# NVME.net
KiCad netlist of a schematic drawn in Altium Designer
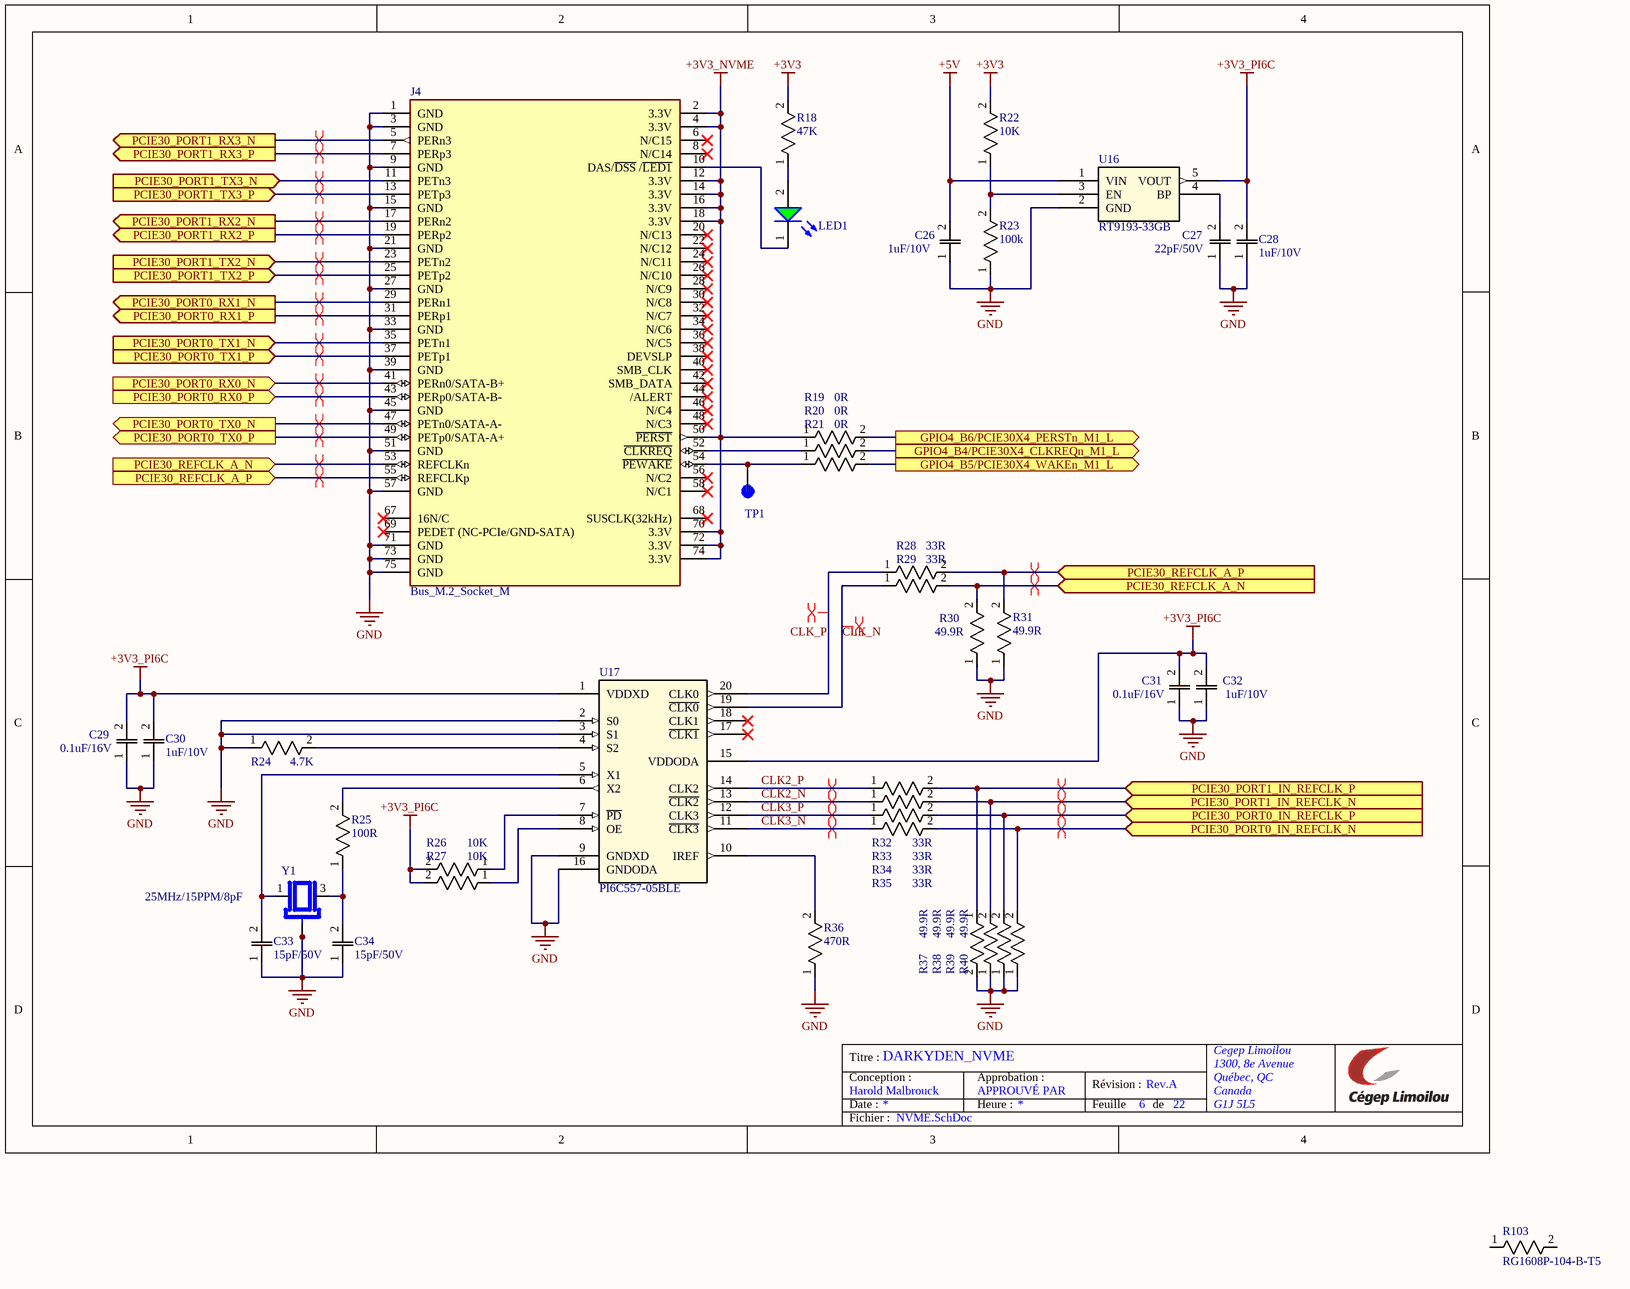
[diagram p0: NVME.SchDoc]

(export (version "E")
  (design (tool "Eeschema 10.0.6"))
  (components
    (comp (ref "C26")
      (value "1uF/10V")
      (footprint "CAPC220145_100N_KEM")
      (description "Multilayer Ceramic Capacitors MLCC - SMD/SMT 10V 1uF X7R 0805 10%")
      (fields
        (field (name "MANUFACTURER") "KEMET")
        (field (name "MANUFACTURER PART NUMBER") "C0805C105K8RACTU")
      )
      (libsource (lib "C0805C105K8RACTU") (part "C0805C105K8RACTU"))
    )
    (comp (ref "C27")
      (value "22pF/50V")
      (footprint "CAPC220145_145N_KEM")
      (description "Cap Ceramic 22pF 50V X7R 5% Pad SMD 0805 125°C T/R")
      (fields
        (field (name "MANUFACTURER") "KEMET")
        (field (name "MANUFACTURER PART NUMBER") "C0805C220J5RACTU")
      )
      (libsource (lib "C0805C220J5RACTU") (part "C0805C220J5RACTU"))
    )
    (comp (ref "C28")
      (value "1uF/10V")
      (footprint "CAPC220145_100N_KEM")
      (description "Multilayer Ceramic Capacitors MLCC - SMD/SMT 10V 1uF X7R 0805 10%")
      (fields
        (field (name "MANUFACTURER") "KEMET")
        (field (name "MANUFACTURER PART NUMBER") "C0805C105K8RACTU")
      )
      (libsource (lib "C0805C105K8RACTU") (part "C0805C105K8RACTU"))
    )
    (comp (ref "C29")
      (value "0.1uF/16V")
      (footprint "CAPC220145_88N_KEM")
      (description "0805 (2012METRIC) Ceramic Capacitor SMD Auto X7R 16V 0.1MUF ±10% X7R")
      (fields
        (field (name "MANUFACTURER") "KEMET")
        (field (name "MANUFACTURER PART NUMBER") "C0805C104K4RACAUTO")
      )
      (libsource (lib "C0805C104K4RACAUTO") (part "C0805C104K4RACAUTO"))
    )
    (comp (ref "C30")
      (value "1uF/10V")
      (footprint "CAPC220145_100N_KEM")
      (description "Multilayer Ceramic Capacitors MLCC - SMD/SMT 10V 1uF X7R 0805 10%")
      (fields
        (field (name "MANUFACTURER") "KEMET")
        (field (name "MANUFACTURER PART NUMBER") "C0805C105K8RACTU")
      )
      (libsource (lib "C0805C105K8RACTU") (part "C0805C105K8RACTU"))
    )
    (comp (ref "C31")
      (value "0.1uF/16V")
      (footprint "CAPC220145_88N_KEM")
      (description "0805 (2012METRIC) Ceramic Capacitor SMD Auto X7R 16V 0.1MUF ±10% X7R")
      (fields
        (field (name "MANUFACTURER") "KEMET")
        (field (name "MANUFACTURER PART NUMBER") "C0805C104K4RACAUTO")
      )
      (libsource (lib "C0805C104K4RACAUTO") (part "C0805C104K4RACAUTO"))
    )
    (comp (ref "C32")
      (value "1uF/10V")
      (footprint "CAPC220145_100N_KEM")
      (description "Multilayer Ceramic Capacitors MLCC - SMD/SMT 10V 1uF X7R 0805 10%")
      (fields
        (field (name "MANUFACTURER") "KEMET")
        (field (name "MANUFACTURER PART NUMBER") "C0805C105K8RACTU")
      )
      (libsource (lib "C0805C105K8RACTU") (part "C0805C105K8RACTU"))
    )
    (comp (ref "C33")
      (value "15pF/50V")
      (footprint "CAPC220145_88N_KEM")
      (description "Multilayer Ceramic Capacitors MLCC - SMD/SMT 50V 15pF X7R 0805 10% AEC-Q200")
      (fields
        (field (name "MANUFACTURER") "KEMET")
        (field (name "MANUFACTURER PART NUMBER") "C0805C150K5RACAUTO")
      )
      (libsource (lib "C0805C150K5RACAUTO") (part "C0805C150K5RACAUTO"))
    )
    (comp (ref "C34")
      (value "15pF/50V")
      (footprint "CAPC220145_88N_KEM")
      (description "Multilayer Ceramic Capacitors MLCC - SMD/SMT 50V 15pF X7R 0805 10% AEC-Q200")
      (fields
        (field (name "MANUFACTURER") "KEMET")
        (field (name "MANUFACTURER PART NUMBER") "C0805C150K5RACAUTO")
      )
      (libsource (lib "C0805C150K5RACAUTO") (part "C0805C150K5RACAUTO"))
    )
    (comp (ref "J4")
      (value "Bus_M.2_Socket_M")
      (footprint "AMPHENOL_MDT420M03001")
      (fields (field (name "MF") "Amphenol Commercial") (field (name "MP") "MDT420M03001"))
      (libsource (lib "Bus_M.2_Socket_M") (part "Bus_M.2_Socket_M"))
    )
    (comp (ref "LED1")
      (value "Green, 3.2V, 140°")
      (footprint "WL-SMCD_0603")
      (description "WL-SMCD Mono-color Chip LED Diffused, SMT, size 0603, Green, 3.2V, 140°")
      (fields
        (field (name "MANUFACTURER PART NUMBER") "150060GS55040")
        (field (name "MANUFACTURER") "Wurth Elektronik")
      )
      (libsource (lib "0603_LED") (part "GREEN"))
    )
    (comp (ref "R18")
      (value "47K")
      (footprint "RC0603N_PAN")
      (description "Resistor Thick Film 0603 47K Ohm 5% 1/10W 200ppm/C Molded SMD Punched Carrier T/R")
      (fields
        (field (name "MANUFACTURER") "Panasonic")
        (field (name "MANUFACTURER PART NUMBER") "ERJ-3GEYJ473V")
      )
      (libsource (lib "ERJ-3GEYJ473V") (part "ERJ-3GEYJ473V"))
    )
    (comp (ref "R19")
      (value "0R")
      (footprint "SamacSys:ERJ3EKF1000V")
      (description "Zero Ohm Resistor, Jumper, 0603 [1608 Metric], Thick Film, 100 mW, 1 A, Surface Mount")
      (fields
        (field (name "MANUFACTURER_PART_NUMBER") "ERJ-3GEY0R00V")
        (field (name "MOUSER PART NUMBER") "667-ERJ-3GEY0R00V")
      )
      (libsource (lib "SamacSys") (part "ERJ-3GEY0R00V"))
    )
    (comp (ref "R20")
      (value "0R")
      (footprint "SamacSys:ERJ3EKF1000V")
      (description "Zero Ohm Resistor, Jumper, 0603 [1608 Metric], Thick Film, 100 mW, 1 A, Surface Mount")
      (fields
        (field (name "MANUFACTURER_PART_NUMBER") "ERJ-3GEY0R00V")
        (field (name "MOUSER PART NUMBER") "667-ERJ-3GEY0R00V")
      )
      (libsource (lib "SamacSys") (part "ERJ-3GEY0R00V"))
    )
    (comp (ref "R21")
      (value "0R")
      (footprint "SamacSys:ERJ3EKF1000V")
      (description "Zero Ohm Resistor, Jumper, 0603 [1608 Metric], Thick Film, 100 mW, 1 A, Surface Mount")
      (fields
        (field (name "MANUFACTURER_PART_NUMBER") "ERJ-3GEY0R00V")
        (field (name "MOUSER PART NUMBER") "667-ERJ-3GEY0R00V")
      )
      (libsource (lib "SamacSys") (part "ERJ-3GEY0R00V"))
    )
    (comp (ref "R22")
      (value "10K")
      (footprint "SamacSys:ERJ3EKF1000V")
      (description "10K Ohm 5% Res Thick Film 0603  0.1W(1/10W) ±200ppm/C Pad SMD Automotive T/R")
      (fields
        (field (name "MANUFACTURER_PART_NUMBER") "ERJ-3GEYJ103V")
        (field (name "MOUSER PART NUMBER") "667-ERJ-3GEYJ103V")
      )
      (libsource (lib "SamacSys") (part "ERJ-3GEYJ103V"))
    )
    (comp (ref "R23")
      (value "100k")
      (footprint "SamacSys:ERJ3EKF1000V")
      (description "100K Ohm 5%  Res Thick Film 0603 1/10W +/-200ppm/ßC Molded SMD Punched Carrier T/R")
      (fields
        (field (name "MANUFACTURER_PART_NUMBER") "ERJ-3GEYJ104V")
        (field (name "MOUSER PART NUMBER") "667-ERJ-3GEYJ104V")
      )
      (libsource (lib "SamacSys") (part "ERJ-3GEYJ104V"))
    )
    (comp (ref "R24")
      (value "4.7K")
      (footprint "RC0603N_PAN")
      (description "Res Thin Film 0603 4.7K Ohm 0.1% 0.1W ±25ppm/°C Molded SMD Punched Carrier T/R")
      (fields
        (field (name "MANUFACTURER") "Panasonic")
        (field (name "MANUFACTURER PART NUMBER") "ERA-3AEB472V")
      )
      (libsource (lib "ERA-3AEB472V") (part "ERA-3AEB472V"))
    )
    (comp (ref "R25")
      (value "100R")
      (footprint "SamacSys:RESC1608X55N")
      (description "100 Ohm 1% 1/10W 0603 ±100ppm/°C Molded SMD Punched Carrier T/R")
      (fields
        (field (name "MANUFACTURER_PART_NUMBER") "ERJ-3EKF1000V")
        (field (name "MOUSER PART NUMBER") "667-ERJ-3EKF1000V")
      )
      (libsource (lib "SamacSys") (part "ERJ-3EKF1000V"))
    )
    (comp (ref "R26")
      (value "10K")
      (footprint "SamacSys:ERJ3EKF1000V")
      (description "10K Ohm 5% Res Thick Film 0603  0.1W(1/10W) ±200ppm/C Pad SMD Automotive T/R")
      (fields
        (field (name "MANUFACTURER_PART_NUMBER") "ERJ-3GEYJ103V")
        (field (name "MOUSER PART NUMBER") "667-ERJ-3GEYJ103V")
      )
      (libsource (lib "SamacSys") (part "ERJ-3GEYJ103V"))
    )
    (comp (ref "R27")
      (value "10K")
      (footprint "SamacSys:ERJ3EKF1000V")
      (description "10K Ohm 5% Res Thick Film 0603  0.1W(1/10W) ±200ppm/C Pad SMD Automotive T/R")
      (fields
        (field (name "MANUFACTURER_PART_NUMBER") "ERJ-3GEYJ103V")
        (field (name "MOUSER PART NUMBER") "667-ERJ-3GEYJ103V")
      )
      (libsource (lib "SamacSys") (part "ERJ-3GEYJ103V"))
    )
    (comp (ref "R28")
      (value "33R")
      (footprint "RC0603N_PAN")
      (description "Res Thick Film 0603 33 Ohm 1% 0.1W ±100ppm/°C Molded SMD Punched Carrier T/R")
      (fields
        (field (name "MANUFACTURER") "Panasonic")
        (field (name "MANUFACTURER PART NUMBER") "ERJ-3EKF33R0V")
      )
      (libsource (lib "ERJ-3EKF33R0V") (part "ERJ-3EKF33R0V"))
    )
    (comp (ref "R29")
      (value "33R")
      (footprint "RC0603N_PAN")
      (description "Res Thick Film 0603 33 Ohm 1% 0.1W ±100ppm/°C Molded SMD Punched Carrier T/R")
      (fields
        (field (name "MANUFACTURER") "Panasonic")
        (field (name "MANUFACTURER PART NUMBER") "ERJ-3EKF33R0V")
      )
      (libsource (lib "ERJ-3EKF33R0V") (part "ERJ-3EKF33R0V"))
    )
    (comp (ref "R30")
      (value "49.9R")
      (footprint "RC0603N_PAN")
      (description "100Mw Thick Film Resistors 100Ppm/ 1% 49.9 0603 Chip Resistor Surface Mount Rohs")
      (fields
        (field (name "MANUFACTURER") "Panasonic")
        (field (name "MANUFACTURER PART NUMBER") "ERJ-3EKF49R9V")
      )
      (libsource (lib "ERJ-3EKF49R9V") (part "ERJ-3EKF49R9V"))
    )
    (comp (ref "R31")
      (value "49.9R")
      (footprint "RC0603N_PAN")
      (description "100Mw Thick Film Resistors 100Ppm/ 1% 49.9 0603 Chip Resistor Surface Mount Rohs")
      (fields
        (field (name "MANUFACTURER") "Panasonic")
        (field (name "MANUFACTURER PART NUMBER") "ERJ-3EKF49R9V")
      )
      (libsource (lib "ERJ-3EKF49R9V") (part "ERJ-3EKF49R9V"))
    )
    (comp (ref "R32")
      (value "33R")
      (footprint "RC0603N_PAN")
      (description "Res Thick Film 0603 33 Ohm 1% 0.1W ±100ppm/°C Molded SMD Punched Carrier T/R")
      (fields
        (field (name "MANUFACTURER") "Panasonic")
        (field (name "MANUFACTURER PART NUMBER") "ERJ-3EKF33R0V")
      )
      (libsource (lib "ERJ-3EKF33R0V") (part "ERJ-3EKF33R0V"))
    )
    (comp (ref "R33")
      (value "33R")
      (footprint "RC0603N_PAN")
      (description "Res Thick Film 0603 33 Ohm 1% 0.1W ±100ppm/°C Molded SMD Punched Carrier T/R")
      (fields
        (field (name "MANUFACTURER") "Panasonic")
        (field (name "MANUFACTURER PART NUMBER") "ERJ-3EKF33R0V")
      )
      (libsource (lib "ERJ-3EKF33R0V") (part "ERJ-3EKF33R0V"))
    )
    (comp (ref "R34")
      (value "33R")
      (footprint "RC0603N_PAN")
      (description "Res Thick Film 0603 33 Ohm 1% 0.1W ±100ppm/°C Molded SMD Punched Carrier T/R")
      (fields
        (field (name "MANUFACTURER") "Panasonic")
        (field (name "MANUFACTURER PART NUMBER") "ERJ-3EKF33R0V")
      )
      (libsource (lib "ERJ-3EKF33R0V") (part "ERJ-3EKF33R0V"))
    )
    (comp (ref "R35")
      (value "33R")
      (footprint "RC0603N_PAN")
      (description "Res Thick Film 0603 33 Ohm 1% 0.1W ±100ppm/°C Molded SMD Punched Carrier T/R")
      (fields
        (field (name "MANUFACTURER") "Panasonic")
        (field (name "MANUFACTURER PART NUMBER") "ERJ-3EKF33R0V")
      )
      (libsource (lib "ERJ-3EKF33R0V") (part "ERJ-3EKF33R0V"))
    )
    (comp (ref "R36")
      (value "470R")
      (footprint "RC0603N_PAN")
      (description "Res Thick Film 0603 470 Ohm 5% 1/10W +/-200ppm/ßC Molded SMD Punched Carrier T/R")
      (fields
        (field (name "MANUFACTURER") "Panasonic")
        (field (name "MANUFACTURER PART NUMBER") "ERJ-3GEYJ471V")
      )
      (libsource (lib "ERJ-3GEYJ471V") (part "ERJ-3GEYJ471V"))
    )
    (comp (ref "R37")
      (value "49.9R")
      (footprint "RC0603N_PAN")
      (description "100Mw Thick Film Resistors 100Ppm/ 1% 49.9 0603 Chip Resistor Surface Mount Rohs")
      (fields
        (field (name "MANUFACTURER") "Panasonic")
        (field (name "MANUFACTURER PART NUMBER") "ERJ-3EKF49R9V")
      )
      (libsource (lib "ERJ-3EKF49R9V") (part "ERJ-3EKF49R9V"))
    )
    (comp (ref "R38")
      (value "49.9R")
      (footprint "RC0603N_PAN")
      (description "100Mw Thick Film Resistors 100Ppm/ 1% 49.9 0603 Chip Resistor Surface Mount Rohs")
      (fields
        (field (name "MANUFACTURER") "Panasonic")
        (field (name "MANUFACTURER PART NUMBER") "ERJ-3EKF49R9V")
      )
      (libsource (lib "ERJ-3EKF49R9V") (part "ERJ-3EKF49R9V"))
    )
    (comp (ref "R39")
      (value "49.9R")
      (footprint "RC0603N_PAN")
      (description "100Mw Thick Film Resistors 100Ppm/ 1% 49.9 0603 Chip Resistor Surface Mount Rohs")
      (fields
        (field (name "MANUFACTURER") "Panasonic")
        (field (name "MANUFACTURER PART NUMBER") "ERJ-3EKF49R9V")
      )
      (libsource (lib "ERJ-3EKF49R9V") (part "ERJ-3EKF49R9V"))
    )
    (comp (ref "R40")
      (value "49.9R")
      (footprint "RC0603N_PAN")
      (description "100Mw Thick Film Resistors 100Ppm/ 1% 49.9 0603 Chip Resistor Surface Mount Rohs")
      (fields
        (field (name "MANUFACTURER") "Panasonic")
        (field (name "MANUFACTURER PART NUMBER") "ERJ-3EKF49R9V")
      )
      (libsource (lib "ERJ-3EKF49R9V") (part "ERJ-3EKF49R9V"))
    )
    (comp (ref "R103")
      (value "RG1608P-104-B-T5")
      (footprint "RES_0816_SUS")
      (description "No Description Available")
      (libsource (lib "RES_SMD_0603") (part "RG1608P-104-B-T5"))
    )
    (comp (ref "TP1")
      (value "5006")
      (footprint "KEYSTONE_5006")
      (description "Test Point Compact THM PC .350 L .125 OD Heat Resistant Nylon 46 Black ¦ Keystone Electronics 5006")
      (fields (field (name "MF") "Keystone Electronics Corp."))
      (libsource (lib "test_point") (part "5006"))
    )
    (comp (ref "U16")
      (value "RT9193-33GB")
      (footprint "SOT-23-5_RIT")
      (description "RT9193 Series 300 mA 3.3 V Ultra-Low Noise Ultra-Fast CMOS LDO Regulator-SC-70-5")
      (fields (field (name "MANUFACTURER") "Richtek"))
      (libsource (lib "RT9193-33GB") (part "RT9193-33GB"))
    )
    (comp (ref "U17")
      (value "PI6C557-05BLE")
      (footprint "L20_PER-M")
      (description "Clock Generators & Support Products PCI express Gen 2 4 output clock gen")
      (fields (field (name "MANUFACTURER") "Diodes"))
      (libsource (lib "PI6C557-05BLE") (part "PI6C557-05BLE"))
    )
    (comp (ref "Y1")
      (value "25MHz/15PPM/8pF")
      (footprint "XTAL_ECS-250-8-37B2-RWY-TR")
      (description "Crystal 25MHz ±15ppm (Tol) ±15ppm (Stability) 8pF FUND 50Ohm 4-Pin Mini-CSMD T/R")
      (fields (field (name "MF") "{'manufacturer': u'ECS Inc.'}") (field (name "MP") "ECS-250-8-37B2-RWY-TR"))
      (libsource (lib "ECS-250-8-37B2-RWY-TR") (part "ECS-250-8-37B2-RWY-TR"))
    )
  )
  (nets
    (net (code "1") (name "+3V3") (class "Default")
      (node (ref "R18") (pin "2") (pinfunction "2_2") (pintype "passive"))
      (node (ref "R22") (pin "2") (pinfunction "2_2") (pintype "passive"))
    )
    (net (code "2") (name "+3V3_NVME") (class "Default")
      (node (ref "J4") (pin "12") (pinfunction "3.3V_12") (pintype "power_in"))
      (node (ref "J4") (pin "14") (pinfunction "3.3V_14") (pintype "power_in"))
      (node (ref "J4") (pin "16") (pinfunction "3.3V_16") (pintype "power_in"))
      (node (ref "J4") (pin "18") (pinfunction "3.3V_18") (pintype "power_in"))
      (node (ref "J4") (pin "2") (pinfunction "3.3V_2") (pintype "power_in"))
      (node (ref "J4") (pin "4") (pinfunction "3.3V_4") (pintype "power_in"))
      (node (ref "J4") (pin "50") (pinfunction "~{PERST}_50") (pintype "output"))
      (node (ref "J4") (pin "70") (pinfunction "3.3V_70") (pintype "power_in"))
      (node (ref "J4") (pin "72") (pinfunction "3.3V_72") (pintype "power_in"))
      (node (ref "J4") (pin "74") (pinfunction "3.3V_74") (pintype "power_in"))
      (node (ref "R19") (pin "1") (pinfunction "1_1") (pintype "passive"))
    )
    (net (code "3") (name "+3V3_PI6C") (class "Default")
      (node (ref "C28") (pin "2") (pinfunction "2_2") (pintype "passive"))
      (node (ref "C29") (pin "2") (pinfunction "2_2") (pintype "passive"))
      (node (ref "C30") (pin "2") (pinfunction "2_2") (pintype "passive"))
      (node (ref "C31") (pin "2") (pinfunction "2_2") (pintype "passive"))
      (node (ref "C32") (pin "2") (pinfunction "2_2") (pintype "passive"))
      (node (ref "R26") (pin "2") (pinfunction "2_2") (pintype "passive"))
      (node (ref "R27") (pin "2") (pinfunction "2_2") (pintype "passive"))
      (node (ref "U16") (pin "5") (pinfunction "VOUT_5") (pintype "output"))
      (node (ref "U17") (pin "1") (pinfunction "VDDXD_1") (pintype "power_in"))
      (node (ref "U17") (pin "15") (pinfunction "VDDODA_15") (pintype "power_in"))
    )
    (net (code "4") (name "+5V") (class "Default")
      (node (ref "C26") (pin "2") (pinfunction "2_2") (pintype "passive"))
      (node (ref "U16") (pin "1") (pinfunction "VIN_1") (pintype "power_in"))
    )
    (net (code "5") (name "/CLK2_N") (class "Default")
      (node (ref "R33") (pin "1") (pinfunction "1_1") (pintype "passive"))
      (node (ref "U17") (pin "13") (pinfunction "~{CLK2}_13") (pintype "output"))
    )
    (net (code "6") (name "/CLK2_P") (class "Default")
      (node (ref "R32") (pin "1") (pinfunction "1_1") (pintype "passive"))
      (node (ref "U17") (pin "14") (pinfunction "CLK2_14") (pintype "output"))
    )
    (net (code "7") (name "/CLK3_N") (class "Default")
      (node (ref "R35") (pin "1") (pinfunction "1_1") (pintype "passive"))
      (node (ref "U17") (pin "11") (pinfunction "~{CLK3}_11") (pintype "output"))
    )
    (net (code "8") (name "/CLK3_P") (class "Default")
      (node (ref "R34") (pin "1") (pinfunction "1_1") (pintype "passive"))
      (node (ref "U17") (pin "12") (pinfunction "CLK3_12") (pintype "output"))
    )
    (net (code "9") (name "/CLK_N") (class "Default")
      (node (ref "R29") (pin "1") (pinfunction "1_1") (pintype "passive"))
      (node (ref "U17") (pin "19") (pinfunction "~{CLK0}_19") (pintype "output"))
    )
    (net (code "10") (name "/CLK_P") (class "Default")
      (node (ref "R28") (pin "1") (pinfunction "1_1") (pintype "passive"))
      (node (ref "U17") (pin "20") (pinfunction "CLK0_20") (pintype "output"))
    )
    (net (code "11") (name "/GPIO4_B4{slash}PCIE30X4_CLKREQn_M1_L") (class "Default")
      (node (ref "R20") (pin "2") (pinfunction "2_2") (pintype "passive"))
    )
    (net (code "12") (name "/GPIO4_B5{slash}PCIE30X4_WAKEn_M1_L") (class "Default")
      (node (ref "R21") (pin "2") (pinfunction "2_2") (pintype "passive"))
    )
    (net (code "13") (name "/GPIO4_B6{slash}PCIE30X4_PERSTn_M1_L") (class "Default")
      (node (ref "R19") (pin "2") (pinfunction "2_2") (pintype "passive"))
    )
    (net (code "14") (name "/PCIE30_PORT0_IN_REFCLK_N") (class "Default")
      (node (ref "R35") (pin "2") (pinfunction "2_2") (pintype "passive"))
      (node (ref "R40") (pin "2") (pinfunction "2_2") (pintype "passive"))
    )
    (net (code "15") (name "/PCIE30_PORT0_IN_REFCLK_P") (class "Default")
      (node (ref "R34") (pin "2") (pinfunction "2_2") (pintype "passive"))
      (node (ref "R39") (pin "2") (pinfunction "2_2") (pintype "passive"))
    )
    (net (code "16") (name "/PCIE30_PORT0_RX0_N") (class "Default")
      (node (ref "J4") (pin "41") (pinfunction "PERn0/SATA-B+_41") (pintype "bidirectional"))
    )
    (net (code "17") (name "/PCIE30_PORT0_RX0_P") (class "Default")
      (node (ref "J4") (pin "43") (pinfunction "PERp0/SATA-B-_43") (pintype "bidirectional"))
    )
    (net (code "18") (name "/PCIE30_PORT0_RX1_N") (class "Default")
      (node (ref "J4") (pin "29") (pinfunction "PERn1_29") (pintype "passive"))
    )
    (net (code "19") (name "/PCIE30_PORT0_RX1_P") (class "Default")
      (node (ref "J4") (pin "31") (pinfunction "PERp1_31") (pintype "passive"))
    )
    (net (code "20") (name "/PCIE30_PORT0_TX0_N") (class "Default")
      (node (ref "J4") (pin "47") (pinfunction "PETn0/SATA-A-_47") (pintype "bidirectional"))
    )
    (net (code "21") (name "/PCIE30_PORT0_TX0_P") (class "Default")
      (node (ref "J4") (pin "49") (pinfunction "PETp0/SATA-A+_49") (pintype "bidirectional"))
    )
    (net (code "22") (name "/PCIE30_PORT0_TX1_N") (class "Default")
      (node (ref "J4") (pin "35") (pinfunction "PETn1_35") (pintype "passive"))
    )
    (net (code "23") (name "/PCIE30_PORT0_TX1_P") (class "Default")
      (node (ref "J4") (pin "37") (pinfunction "PETp1_37") (pintype "passive"))
    )
    (net (code "24") (name "/PCIE30_PORT1_IN_REFCLK_N") (class "Default")
      (node (ref "R33") (pin "2") (pinfunction "2_2") (pintype "passive"))
      (node (ref "R38") (pin "2") (pinfunction "2_2") (pintype "passive"))
    )
    (net (code "25") (name "/PCIE30_PORT1_IN_REFCLK_P") (class "Default")
      (node (ref "R32") (pin "2") (pinfunction "2_2") (pintype "passive"))
      (node (ref "R37") (pin "1") (pinfunction "1_1") (pintype "passive"))
    )
    (net (code "26") (name "/PCIE30_PORT1_RX2_N") (class "Default")
      (node (ref "J4") (pin "17") (pinfunction "PERn2_17") (pintype "passive"))
    )
    (net (code "27") (name "/PCIE30_PORT1_RX2_P") (class "Default")
      (node (ref "J4") (pin "19") (pinfunction "PERp2_19") (pintype "passive"))
    )
    (net (code "28") (name "/PCIE30_PORT1_RX3_N") (class "Default")
      (node (ref "J4") (pin "5") (pinfunction "PERn3_5") (pintype "output"))
    )
    (net (code "29") (name "/PCIE30_PORT1_RX3_P") (class "Default")
      (node (ref "J4") (pin "7") (pinfunction "PERp3_7") (pintype "passive"))
    )
    (net (code "30") (name "/PCIE30_PORT1_TX2_N") (class "Default")
      (node (ref "J4") (pin "23") (pinfunction "PETn2_23") (pintype "passive"))
    )
    (net (code "31") (name "/PCIE30_PORT1_TX2_P") (class "Default")
      (node (ref "J4") (pin "25") (pinfunction "PETp2_25") (pintype "passive"))
    )
    (net (code "32") (name "/PCIE30_PORT1_TX3_N") (class "Default")
      (node (ref "J4") (pin "11") (pinfunction "PETn3_11") (pintype "passive"))
    )
    (net (code "33") (name "/PCIE30_PORT1_TX3_P") (class "Default")
      (node (ref "J4") (pin "13") (pinfunction "PETp3_13") (pintype "passive"))
    )
    (net (code "34") (name "/PCIE30_REFCLK_A_N") (class "Default")
      (node (ref "J4") (pin "53") (pinfunction "REFCLKn_53") (pintype "bidirectional"))
      (node (ref "R29") (pin "2") (pinfunction "2_2") (pintype "passive"))
      (node (ref "R30") (pin "2") (pinfunction "2_2") (pintype "passive"))
    )
    (net (code "35") (name "/PCIE30_REFCLK_A_P") (class "Default")
      (node (ref "J4") (pin "55") (pinfunction "REFCLKp_55") (pintype "bidirectional"))
      (node (ref "R28") (pin "2") (pinfunction "2_2") (pintype "passive"))
      (node (ref "R31") (pin "2") (pinfunction "2_2") (pintype "passive"))
    )
    (net (code "36") (name "GND") (class "Default")
      (node (ref "C26") (pin "1") (pinfunction "1_1") (pintype "passive"))
      (node (ref "C27") (pin "1") (pinfunction "1_1") (pintype "passive"))
      (node (ref "C28") (pin "1") (pinfunction "1_1") (pintype "passive"))
      (node (ref "C29") (pin "1") (pinfunction "1_1") (pintype "passive"))
      (node (ref "C30") (pin "1") (pinfunction "1_1") (pintype "passive"))
      (node (ref "C31") (pin "1") (pinfunction "1_1") (pintype "passive"))
      (node (ref "C32") (pin "1") (pinfunction "1_1") (pintype "passive"))
      (node (ref "C33") (pin "1") (pinfunction "1_1") (pintype "passive"))
      (node (ref "C34") (pin "1") (pinfunction "1_1") (pintype "passive"))
      (node (ref "J4") (pin "1") (pinfunction "GND_1") (pintype "passive"))
      (node (ref "J4") (pin "15") (pinfunction "GND_15") (pintype "passive"))
      (node (ref "J4") (pin "21") (pinfunction "GND_21") (pintype "passive"))
      (node (ref "J4") (pin "27") (pinfunction "GND_27") (pintype "passive"))
      (node (ref "J4") (pin "3") (pinfunction "GND_3") (pintype "passive"))
      (node (ref "J4") (pin "33") (pinfunction "GND_33") (pintype "passive"))
      (node (ref "J4") (pin "39") (pinfunction "GND_39") (pintype "passive"))
      (node (ref "J4") (pin "45") (pinfunction "GND_45") (pintype "passive"))
      (node (ref "J4") (pin "51") (pinfunction "GND_51") (pintype "passive"))
      (node (ref "J4") (pin "57") (pinfunction "GND_57") (pintype "passive"))
      (node (ref "J4") (pin "71") (pinfunction "GND_71") (pintype "passive"))
      (node (ref "J4") (pin "73") (pinfunction "GND_73") (pintype "passive"))
      (node (ref "J4") (pin "75") (pinfunction "GND_75") (pintype "passive"))
      (node (ref "J4") (pin "9") (pinfunction "GND_9") (pintype "passive"))
      (node (ref "R23") (pin "1") (pinfunction "1_1") (pintype "passive"))
      (node (ref "R24") (pin "1") (pinfunction "1_1") (pintype "passive"))
      (node (ref "R30") (pin "1") (pinfunction "1_1") (pintype "passive"))
      (node (ref "R31") (pin "1") (pinfunction "1_1") (pintype "passive"))
      (node (ref "R36") (pin "1") (pinfunction "1_1") (pintype "passive"))
      (node (ref "R37") (pin "2") (pinfunction "2_2") (pintype "passive"))
      (node (ref "R38") (pin "1") (pinfunction "1_1") (pintype "passive"))
      (node (ref "R39") (pin "1") (pinfunction "1_1") (pintype "passive"))
      (node (ref "R40") (pin "1") (pinfunction "1_1") (pintype "passive"))
      (node (ref "U16") (pin "2") (pinfunction "GND_2") (pintype "passive"))
      (node (ref "U17") (pin "16") (pinfunction "GNDODA_16") (pintype "passive"))
      (node (ref "U17") (pin "2") (pinfunction "S0_2") (pintype "input"))
      (node (ref "U17") (pin "3") (pinfunction "S1_3") (pintype "input"))
      (node (ref "U17") (pin "9") (pinfunction "GNDXD_9") (pintype "passive"))
      (node (ref "Y1") (pin "2") (pinfunction "GND_2") (pintype "power_in"))
      (node (ref "Y1") (pin "4") (pinfunction "GND_4") (pintype "power_in"))
    )
    (net (code "37") (name "Net-(J4-DAS{slash}~{DSS}_{slash}~{LED1})") (class "Default")
      (node (ref "J4") (pin "10") (pinfunction "DAS/~{DSS}_/~{LED1}_10") (pintype "passive"))
      (node (ref "LED1") (pin "1") (pinfunction "K_1") (pintype "passive"))
    )
    (net (code "38") (name "Net-(J4-~{CLKREQ})") (class "Default")
      (node (ref "J4") (pin "52") (pinfunction "~{CLKREQ}_52") (pintype "bidirectional"))
      (node (ref "R20") (pin "1") (pinfunction "1_1") (pintype "passive"))
    )
    (net (code "39") (name "Net-(J4-~{PEWAKE})") (class "Default")
      (node (ref "J4") (pin "54") (pinfunction "~{PEWAKE}_54") (pintype "bidirectional"))
      (node (ref "R21") (pin "1") (pinfunction "1_1") (pintype "passive"))
      (node (ref "TP1") (pin "TP") (pinfunction "TP_TP") (pintype "passive"))
    )
    (net (code "40") (name "Net-(LED1-A)") (class "Default")
      (node (ref "LED1") (pin "2") (pinfunction "A_2") (pintype "passive"))
      (node (ref "R18") (pin "1") (pinfunction "1_1") (pintype "passive"))
    )
    (net (code "41") (name "Net-(U16-BP)") (class "Default")
      (node (ref "C27") (pin "2") (pinfunction "2_2") (pintype "passive"))
      (node (ref "U16") (pin "4") (pinfunction "BP_4") (pintype "passive"))
    )
    (net (code "42") (name "Net-(U16-EN)") (class "Default")
      (node (ref "R22") (pin "1") (pinfunction "1_1") (pintype "passive"))
      (node (ref "R23") (pin "2") (pinfunction "2_2") (pintype "passive"))
      (node (ref "U16") (pin "3") (pinfunction "EN_3") (pintype "passive"))
    )
    (net (code "43") (name "Net-(U17-IREF)") (class "Default")
      (node (ref "R36") (pin "2") (pinfunction "2_2") (pintype "passive"))
      (node (ref "U17") (pin "10") (pinfunction "IREF_10") (pintype "output"))
    )
    (net (code "44") (name "Net-(U17-OE)") (class "Default")
      (node (ref "R27") (pin "1") (pinfunction "1_1") (pintype "passive"))
      (node (ref "U17") (pin "8") (pinfunction "OE_8") (pintype "input"))
    )
    (net (code "45") (name "Net-(U17-S2)") (class "Default")
      (node (ref "R24") (pin "2") (pinfunction "2_2") (pintype "passive"))
      (node (ref "U17") (pin "4") (pinfunction "S2_4") (pintype "input"))
    )
    (net (code "46") (name "Net-(U17-X1)") (class "Default")
      (node (ref "C33") (pin "2") (pinfunction "2_2") (pintype "passive"))
      (node (ref "U17") (pin "5") (pinfunction "X1_5") (pintype "input"))
      (node (ref "Y1") (pin "1") (pinfunction "IN/OUT_1") (pintype "passive"))
    )
    (net (code "47") (name "Net-(U17-X2)") (class "Default")
      (node (ref "R25") (pin "2") (pinfunction "2_2") (pintype "passive"))
      (node (ref "U17") (pin "6") (pinfunction "X2_6") (pintype "output"))
    )
    (net (code "48") (name "Net-(U17-~{PD})") (class "Default")
      (node (ref "R26") (pin "1") (pinfunction "1_1") (pintype "passive"))
      (node (ref "U17") (pin "7") (pinfunction "~{PD}_7") (pintype "input"))
    )
    (net (code "49") (name "Net-(Y1-OUT{slash}IN)") (class "Default")
      (node (ref "C34") (pin "2") (pinfunction "2_2") (pintype "passive"))
      (node (ref "R25") (pin "1") (pinfunction "1_1") (pintype "passive"))
      (node (ref "Y1") (pin "3") (pinfunction "OUT/IN_3") (pintype "passive"))
    )
    (net (code "50") (name "unconnected-(J4-16N{slash}C-Pad67)") (class "Default")
      (node (ref "J4") (pin "67") (pinfunction "16N/C_67") (pintype "passive+no_connect"))
    )
    (net (code "51") (name "unconnected-(J4-DEVSLP-Pad38)") (class "Default")
      (node (ref "J4") (pin "38") (pinfunction "DEVSLP_38") (pintype "passive+no_connect"))
    )
    (net (code "52") (name "unconnected-(J4-N{slash}C1-Pad58)") (class "Default")
      (node (ref "J4") (pin "58") (pinfunction "N/C1_58") (pintype "passive+no_connect"))
    )
    (net (code "53") (name "unconnected-(J4-N{slash}C2-Pad56)") (class "Default")
      (node (ref "J4") (pin "56") (pinfunction "N/C2_56") (pintype "passive+no_connect"))
    )
    (net (code "54") (name "unconnected-(J4-N{slash}C3-Pad48)") (class "Default")
      (node (ref "J4") (pin "48") (pinfunction "N/C3_48") (pintype "passive+no_connect"))
    )
    (net (code "55") (name "unconnected-(J4-N{slash}C4-Pad46)") (class "Default")
      (node (ref "J4") (pin "46") (pinfunction "N/C4_46") (pintype "passive+no_connect"))
    )
    (net (code "56") (name "unconnected-(J4-N{slash}C5-Pad36)") (class "Default")
      (node (ref "J4") (pin "36") (pinfunction "N/C5_36") (pintype "passive+no_connect"))
    )
    (net (code "57") (name "unconnected-(J4-N{slash}C6-Pad34)") (class "Default")
      (node (ref "J4") (pin "34") (pinfunction "N/C6_34") (pintype "passive+no_connect"))
    )
    (net (code "58") (name "unconnected-(J4-N{slash}C7-Pad32)") (class "Default")
      (node (ref "J4") (pin "32") (pinfunction "N/C7_32") (pintype "passive+no_connect"))
    )
    (net (code "59") (name "unconnected-(J4-N{slash}C8-Pad30)") (class "Default")
      (node (ref "J4") (pin "30") (pinfunction "N/C8_30") (pintype "passive+no_connect"))
    )
    (net (code "60") (name "unconnected-(J4-N{slash}C9-Pad28)") (class "Default")
      (node (ref "J4") (pin "28") (pinfunction "N/C9_28") (pintype "passive+no_connect"))
    )
    (net (code "61") (name "unconnected-(J4-N{slash}C10-Pad26)") (class "Default")
      (node (ref "J4") (pin "26") (pinfunction "N/C10_26") (pintype "passive+no_connect"))
    )
    (net (code "62") (name "unconnected-(J4-N{slash}C11-Pad24)") (class "Default")
      (node (ref "J4") (pin "24") (pinfunction "N/C11_24") (pintype "passive+no_connect"))
    )
    (net (code "63") (name "unconnected-(J4-N{slash}C12-Pad22)") (class "Default")
      (node (ref "J4") (pin "22") (pinfunction "N/C12_22") (pintype "passive+no_connect"))
    )
    (net (code "64") (name "unconnected-(J4-N{slash}C13-Pad20)") (class "Default")
      (node (ref "J4") (pin "20") (pinfunction "N/C13_20") (pintype "passive+no_connect"))
    )
    (net (code "65") (name "unconnected-(J4-N{slash}C14-Pad8)") (class "Default")
      (node (ref "J4") (pin "8") (pinfunction "N/C14_8") (pintype "passive+no_connect"))
    )
    (net (code "66") (name "unconnected-(J4-N{slash}C15-Pad6)") (class "Default")
      (node (ref "J4") (pin "6") (pinfunction "N/C15_6") (pintype "passive+no_connect"))
    )
    (net (code "67") (name "unconnected-(J4-PEDET_(NC-PCIe{slash}GND-SATA)-Pad69)") (class "Default")
      (node (ref "J4") (pin "69") (pinfunction "PEDET_(NC-PCIe/GND-SATA)_69") (pintype "passive+no_connect"))
    )
    (net (code "68") (name "unconnected-(J4-SMB_CLK-Pad40)") (class "Default")
      (node (ref "J4") (pin "40") (pinfunction "SMB_CLK_40") (pintype "passive+no_connect"))
    )
    (net (code "69") (name "unconnected-(J4-SMB_DATA-Pad42)") (class "Default")
      (node (ref "J4") (pin "42") (pinfunction "SMB_DATA_42") (pintype "passive+no_connect"))
    )
    (net (code "70") (name "unconnected-(J4-SUSCLK(32kHz)-Pad68)") (class "Default")
      (node (ref "J4") (pin "68") (pinfunction "SUSCLK(32kHz)_68") (pintype "passive+no_connect"))
    )
    (net (code "71") (name "unconnected-(J4-{slash}ALERT-Pad44)") (class "Default")
      (node (ref "J4") (pin "44") (pinfunction "/ALERT_44") (pintype "passive+no_connect"))
    )
    (net (code "72") (name "unconnected-(R103-Pad1)") (class "Default")
      (node (ref "R103") (pin "1") (pinfunction "1_1") (pintype "passive"))
    )
    (net (code "73") (name "unconnected-(R103-Pad2)") (class "Default")
      (node (ref "R103") (pin "2") (pinfunction "2_2") (pintype "passive"))
    )
    (net (code "74") (name "unconnected-(U17-CLK1-Pad18)") (class "Default")
      (node (ref "U17") (pin "18") (pinfunction "CLK1_18") (pintype "output+no_connect"))
    )
    (net (code "75") (name "unconnected-(U17-~{CLK1}-Pad17)") (class "Default")
      (node (ref "U17") (pin "17") (pinfunction "~{CLK1}_17") (pintype "output+no_connect"))
    )
  )
)
